# sdo_to_quiic_qt_led.net
KiCad netlist of a schematic drawn in EAGLE
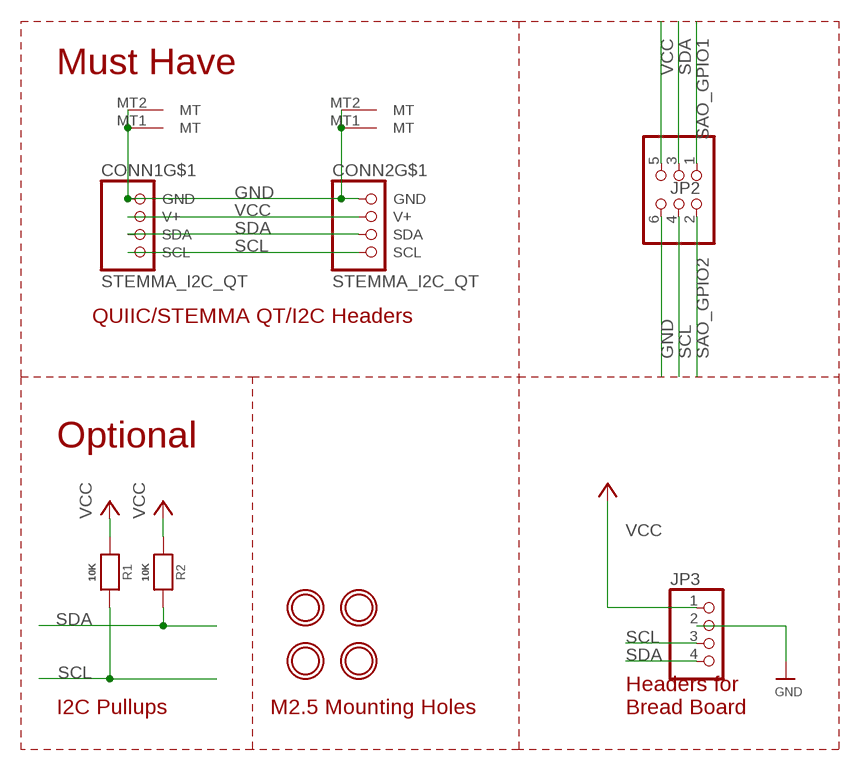
[diagram p0: schematic, sheet 1]

(export (version "E")
  (design (tool "Eeschema 10.0.6"))
  (components
    (comp (ref "CONN1")
      (value "STEMMA_I2C_QT")
      (footprint "eagle-import:JST_SH4")
      (libsource (lib "eagle-import") (part "STEMMA_I2C_QT"))
    )
    (comp (ref "CONN2")
      (value "STEMMA_I2C_QT")
      (footprint "eagle-import:JST_SH4")
      (libsource (lib "eagle-import") (part "STEMMA_I2C_QT"))
    )
    (comp (ref "JP2")
      (value "HEADER-2X3")
      (footprint "eagle-import:2X03_ROUND_70MIL")
      (libsource (lib "eagle-import") (part "HEADER-2X3"))
    )
    (comp (ref "JP3")
      (value "HEADER-1X4ROUND")
      (footprint "eagle-import:1X04_ROUND")
      (libsource (lib "eagle-import") (part "HEADER-1X4ROUND"))
    )
    (comp (ref "R1")
      (value "10K")
      (footprint "eagle-import:0805-NO")
      (libsource (lib "eagle-import") (part "RESISTOR0805_NOOUTLINE"))
    )
    (comp (ref "R2")
      (value "10K")
      (footprint "eagle-import:0805-NO")
      (libsource (lib "eagle-import") (part "RESISTOR0805_NOOUTLINE"))
    )
    (comp (ref "U$1")
      (value "MOUNTINGHOLE2.5")
      (footprint "eagle-import:MOUNTINGHOLE_2.5_PLATED")
      (libsource (lib "eagle-import") (part "MOUNTINGHOLE2.5"))
    )
    (comp (ref "U$17")
      (value "MOUNTINGHOLE2.5")
      (footprint "eagle-import:MOUNTINGHOLE_2.5_PLATED")
      (libsource (lib "eagle-import") (part "MOUNTINGHOLE2.5"))
    )
    (comp (ref "U$19")
      (value "MOUNTINGHOLE2.5")
      (footprint "eagle-import:MOUNTINGHOLE_2.5_PLATED")
      (libsource (lib "eagle-import") (part "MOUNTINGHOLE2.5"))
    )
    (comp (ref "U$21")
      (value "MOUNTINGHOLE2.5")
      (footprint "eagle-import:MOUNTINGHOLE_2.5_PLATED")
      (libsource (lib "eagle-import") (part "MOUNTINGHOLE2.5"))
    )
  )
  (nets
    (net (code "1") (name "/SAO_GPIO1") (class "Default")
      (node (ref "JP2") (pin "1") (pinfunction "1_1") (pintype "passive"))
    )
    (net (code "2") (name "/SAO_GPIO2") (class "Default")
      (node (ref "JP2") (pin "2") (pinfunction "2_2") (pintype "passive"))
    )
    (net (code "3") (name "/SCL") (class "Default")
      (node (ref "CONN1") (pin "4") (pinfunction "SCL_4") (pintype "passive"))
      (node (ref "CONN2") (pin "4") (pinfunction "SCL_4") (pintype "passive"))
      (node (ref "JP2") (pin "4") (pinfunction "4_4") (pintype "passive"))
      (node (ref "JP3") (pin "3") (pinfunction "3_3") (pintype "passive"))
      (node (ref "R1") (pin "2") (pinfunction "2_2") (pintype "passive"))
    )
    (net (code "4") (name "/SDA") (class "Default")
      (node (ref "CONN1") (pin "3") (pinfunction "SDA_3") (pintype "passive"))
      (node (ref "CONN2") (pin "3") (pinfunction "SDA_3") (pintype "passive"))
      (node (ref "JP2") (pin "3") (pinfunction "3_3") (pintype "passive"))
      (node (ref "JP3") (pin "4") (pinfunction "4_4") (pintype "passive"))
      (node (ref "R2") (pin "2") (pinfunction "2_2") (pintype "passive"))
    )
    (net (code "5") (name "GND") (class "Default")
      (node (ref "CONN1") (pin "1") (pinfunction "GND_1") (pintype "passive"))
      (node (ref "CONN1") (pin "MT1") (pinfunction "MT_MT1") (pintype "bidirectional"))
      (node (ref "CONN1") (pin "MT2") (pinfunction "MT_MT2") (pintype "bidirectional"))
      (node (ref "CONN2") (pin "1") (pinfunction "GND_1") (pintype "passive"))
      (node (ref "CONN2") (pin "MT1") (pinfunction "MT_MT1") (pintype "bidirectional"))
      (node (ref "CONN2") (pin "MT2") (pinfunction "MT_MT2") (pintype "bidirectional"))
      (node (ref "JP2") (pin "6") (pinfunction "6_6") (pintype "passive"))
      (node (ref "JP3") (pin "2") (pinfunction "2_2") (pintype "passive"))
    )
    (net (code "6") (name "VCC") (class "Default")
      (node (ref "CONN1") (pin "2") (pinfunction "V+_2") (pintype "passive"))
      (node (ref "CONN2") (pin "2") (pinfunction "V+_2") (pintype "passive"))
      (node (ref "JP2") (pin "5") (pinfunction "5_5") (pintype "passive"))
      (node (ref "JP3") (pin "1") (pinfunction "1_1") (pintype "passive"))
      (node (ref "R1") (pin "1") (pinfunction "1_1") (pintype "passive"))
      (node (ref "R2") (pin "1") (pinfunction "1_1") (pintype "passive"))
    )
  )
)
